# Busbar.net
KiCad netlist of a schematic drawn in Altium Designer
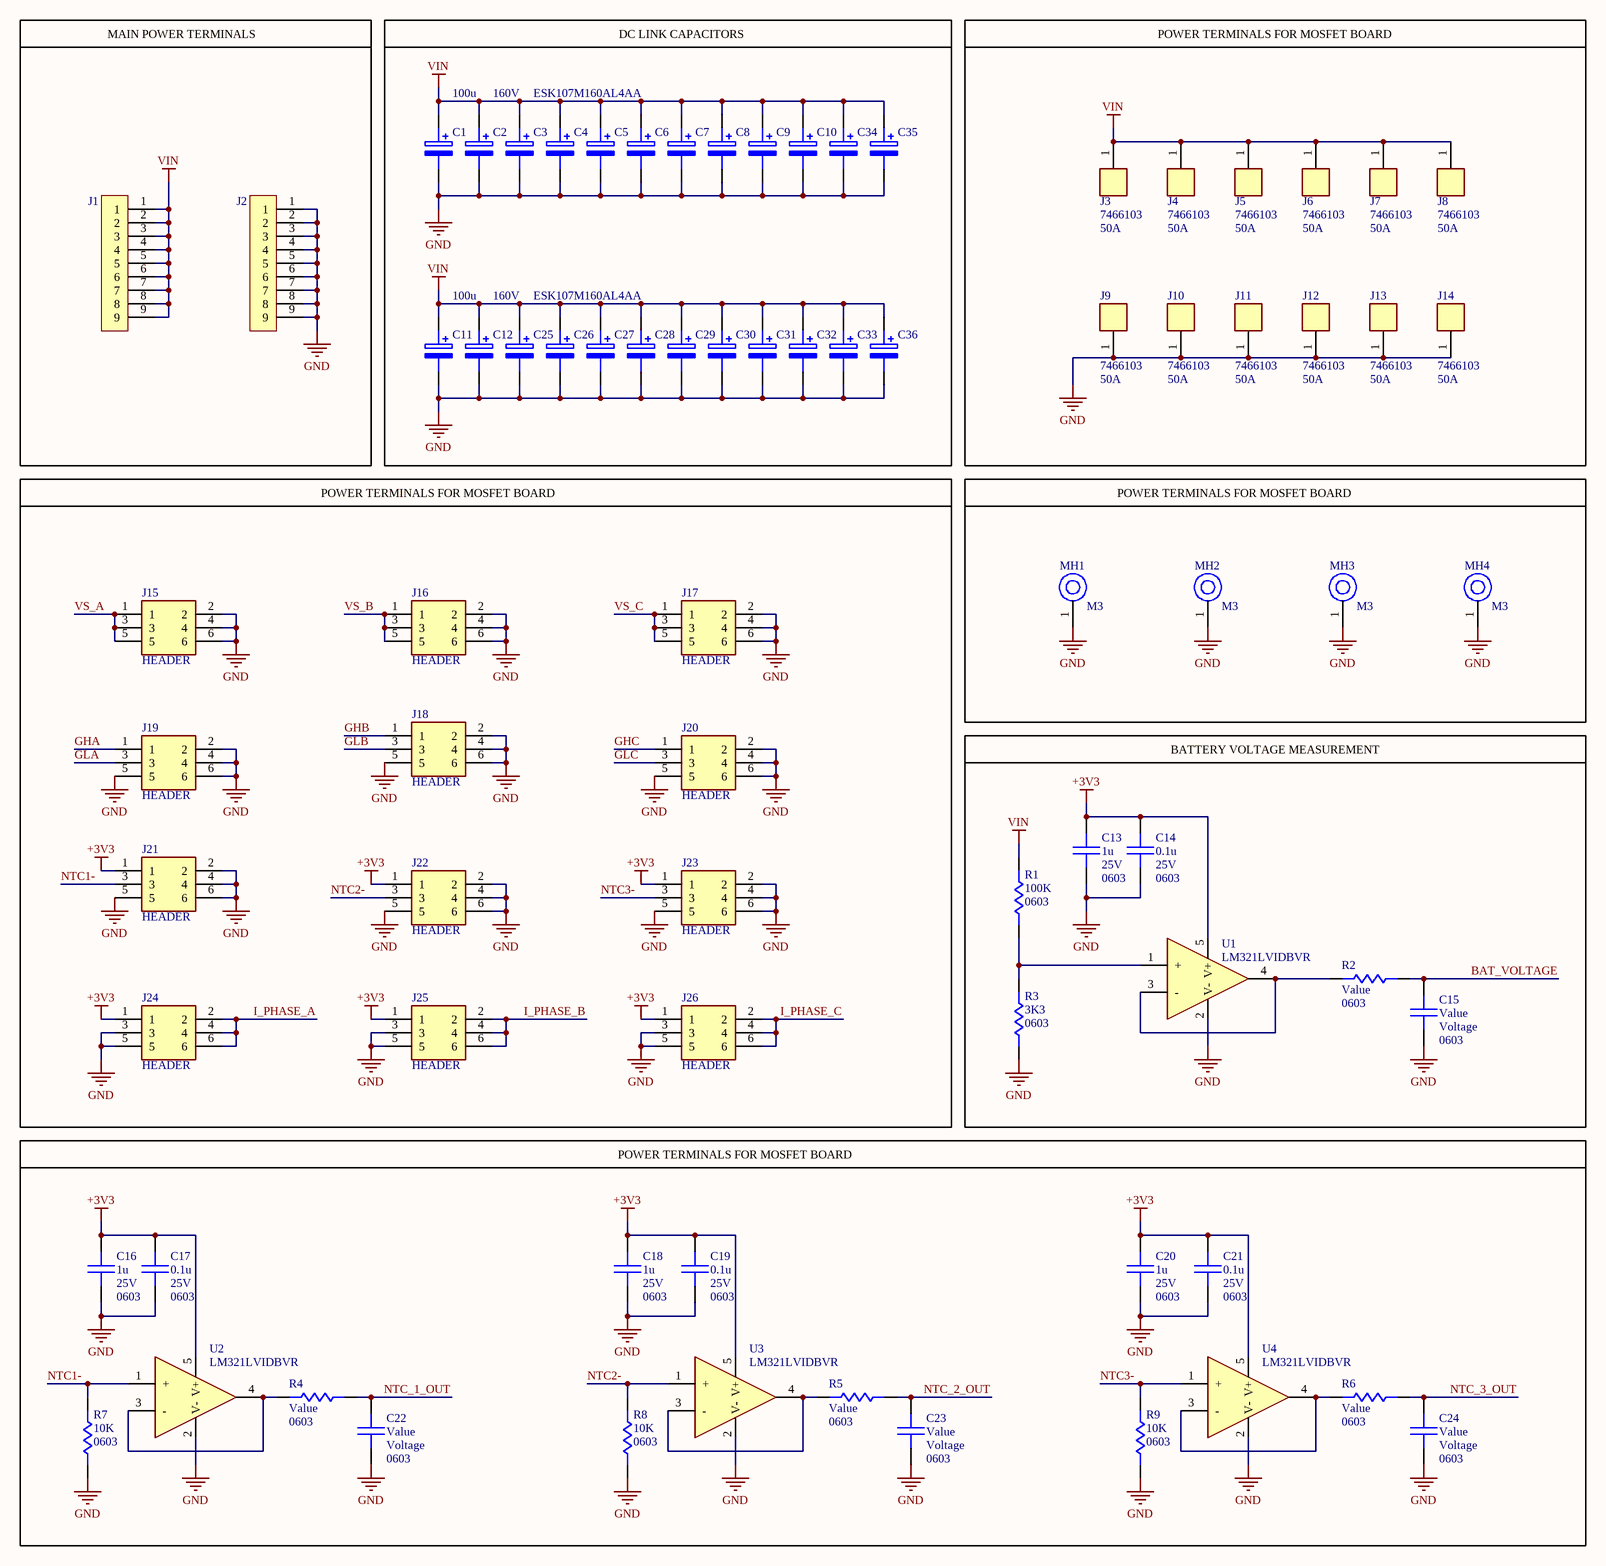
[diagram p0: Busbar.SchDoc]

(export (version "E")
  (design (tool "Eeschema 10.0.6"))
  (components
    (comp (ref "C1")
      (value "ESK107M160AL4AA")
      (footprint "C_THT_13X25X5")
      (description "Capacitor Polarised")
      (fields (field (name "ALTIUM_VALUE") "100u") (field (name "VOLTAGE") "160V"))
      (libsource (lib "My_Integrated_Lib") (part "CAP_POL_THT_100u_160V"))
    )
    (comp (ref "C2")
      (value "ESK107M160AL4AA")
      (footprint "C_THT_13X25X5")
      (description "Capacitor Polarised")
      (fields (field (name "VOLTAGE") "160V"))
      (libsource (lib "My_Integrated_Lib") (part "CAP_POL_THT_100u_160V"))
    )
    (comp (ref "C3")
      (value "ESK107M160AL4AA")
      (footprint "C_THT_13X25X5")
      (description "Capacitor Polarised")
      (fields (field (name "VOLTAGE") "160V"))
      (libsource (lib "My_Integrated_Lib") (part "CAP_POL_THT_100u_160V"))
    )
    (comp (ref "C4")
      (value "ESK107M160AL4AA")
      (footprint "C_THT_13X25X5")
      (description "Capacitor Polarised")
      (fields (field (name "VOLTAGE") "160V"))
      (libsource (lib "My_Integrated_Lib") (part "CAP_POL_THT_100u_160V"))
    )
    (comp (ref "C5")
      (value "ESK107M160AL4AA")
      (footprint "C_THT_13X25X5")
      (description "Capacitor Polarised")
      (fields (field (name "VOLTAGE") "160V"))
      (libsource (lib "My_Integrated_Lib") (part "CAP_POL_THT_100u_160V"))
    )
    (comp (ref "C6")
      (value "ESK107M160AL4AA")
      (footprint "C_THT_13X25X5")
      (description "Capacitor Polarised")
      (fields (field (name "VOLTAGE") "160V"))
      (libsource (lib "My_Integrated_Lib") (part "CAP_POL_THT_100u_160V"))
    )
    (comp (ref "C7")
      (value "ESK107M160AL4AA")
      (footprint "C_THT_13X25X5")
      (description "Capacitor Polarised")
      (fields (field (name "VOLTAGE") "160V"))
      (libsource (lib "My_Integrated_Lib") (part "CAP_POL_THT_100u_160V"))
    )
    (comp (ref "C8")
      (value "ESK107M160AL4AA")
      (footprint "C_THT_13X25X5")
      (description "Capacitor Polarised")
      (fields (field (name "VOLTAGE") "160V"))
      (libsource (lib "My_Integrated_Lib") (part "CAP_POL_THT_100u_160V"))
    )
    (comp (ref "C9")
      (value "ESK107M160AL4AA")
      (footprint "C_THT_13X25X5")
      (description "Capacitor Polarised")
      (fields (field (name "VOLTAGE") "160V"))
      (libsource (lib "My_Integrated_Lib") (part "CAP_POL_THT_100u_160V"))
    )
    (comp (ref "C10")
      (value "ESK107M160AL4AA")
      (footprint "C_THT_13X25X5")
      (description "Capacitor Polarised")
      (fields (field (name "VOLTAGE") "160V"))
      (libsource (lib "My_Integrated_Lib") (part "CAP_POL_THT_100u_160V"))
    )
    (comp (ref "C11")
      (value "ESK107M160AL4AA")
      (footprint "C_THT_13X25X5")
      (description "Capacitor Polarised")
      (fields (field (name "ALTIUM_VALUE") "100u") (field (name "VOLTAGE") "160V"))
      (libsource (lib "My_Integrated_Lib") (part "CAP_POL_THT_100u_160V"))
    )
    (comp (ref "C12")
      (value "ESK107M160AL4AA")
      (footprint "C_THT_13X25X5")
      (description "Capacitor Polarised")
      (fields (field (name "VOLTAGE") "160V"))
      (libsource (lib "My_Integrated_Lib") (part "CAP_POL_THT_100u_160V"))
    )
    (comp (ref "C13")
      (value "0603")
      (footprint "C_0603")
      (description "SMD Chip Capacitor - 0603")
      (fields (field (name "VOLTAGE") "25V") (field (name "ALTIUM_VALUE") "1u"))
      (libsource (lib "My_Integrated_Lib") (part "CAP_0603"))
    )
    (comp (ref "C14")
      (value "0603")
      (footprint "C_0603")
      (description "SMD Chip Capacitor - 0603")
      (fields (field (name "VOLTAGE") "25V") (field (name "ALTIUM_VALUE") "0.1u"))
      (libsource (lib "My_Integrated_Lib") (part "CAP_0603"))
    )
    (comp (ref "C15")
      (value "0603")
      (footprint "C_0603")
      (description "SMD Chip Capacitor - 0603")
      (fields (field (name "VOLTAGE") "Voltage") (field (name "ALTIUM_VALUE") "Value"))
      (libsource (lib "My_Integrated_Lib") (part "CAP_0603"))
    )
    (comp (ref "C16")
      (value "0603")
      (footprint "C_0603")
      (description "SMD Chip Capacitor - 0603")
      (fields (field (name "VOLTAGE") "25V") (field (name "ALTIUM_VALUE") "1u"))
      (libsource (lib "My_Integrated_Lib") (part "CAP_0603"))
    )
    (comp (ref "C17")
      (value "0603")
      (footprint "C_0603")
      (description "SMD Chip Capacitor - 0603")
      (fields (field (name "VOLTAGE") "25V") (field (name "ALTIUM_VALUE") "0.1u"))
      (libsource (lib "My_Integrated_Lib") (part "CAP_0603"))
    )
    (comp (ref "C18")
      (value "0603")
      (footprint "C_0603")
      (description "SMD Chip Capacitor - 0603")
      (fields (field (name "VOLTAGE") "25V") (field (name "ALTIUM_VALUE") "1u"))
      (libsource (lib "My_Integrated_Lib") (part "CAP_0603"))
    )
    (comp (ref "C19")
      (value "0603")
      (footprint "C_0603")
      (description "SMD Chip Capacitor - 0603")
      (fields (field (name "VOLTAGE") "25V") (field (name "ALTIUM_VALUE") "0.1u"))
      (libsource (lib "My_Integrated_Lib") (part "CAP_0603"))
    )
    (comp (ref "C20")
      (value "0603")
      (footprint "C_0603")
      (description "SMD Chip Capacitor - 0603")
      (fields (field (name "VOLTAGE") "25V") (field (name "ALTIUM_VALUE") "1u"))
      (libsource (lib "My_Integrated_Lib") (part "CAP_0603"))
    )
    (comp (ref "C21")
      (value "0603")
      (footprint "C_0603")
      (description "SMD Chip Capacitor - 0603")
      (fields (field (name "VOLTAGE") "25V") (field (name "ALTIUM_VALUE") "0.1u"))
      (libsource (lib "My_Integrated_Lib") (part "CAP_0603"))
    )
    (comp (ref "C22")
      (value "0603")
      (footprint "C_0603")
      (description "SMD Chip Capacitor - 0603")
      (fields (field (name "VOLTAGE") "Voltage") (field (name "ALTIUM_VALUE") "Value"))
      (libsource (lib "My_Integrated_Lib") (part "CAP_0603"))
    )
    (comp (ref "C23")
      (value "0603")
      (footprint "C_0603")
      (description "SMD Chip Capacitor - 0603")
      (fields (field (name "VOLTAGE") "Voltage") (field (name "ALTIUM_VALUE") "Value"))
      (libsource (lib "My_Integrated_Lib") (part "CAP_0603"))
    )
    (comp (ref "C24")
      (value "0603")
      (footprint "C_0603")
      (description "SMD Chip Capacitor - 0603")
      (fields (field (name "VOLTAGE") "Voltage") (field (name "ALTIUM_VALUE") "Value"))
      (libsource (lib "My_Integrated_Lib") (part "CAP_0603"))
    )
    (comp (ref "C25")
      (value "ESK107M160AL4AA")
      (footprint "C_THT_13X25X5")
      (description "Capacitor Polarised")
      (fields (field (name "VOLTAGE") "160V"))
      (libsource (lib "My_Integrated_Lib") (part "CAP_POL_THT_100u_160V"))
    )
    (comp (ref "C26")
      (value "ESK107M160AL4AA")
      (footprint "C_THT_13X25X5")
      (description "Capacitor Polarised")
      (fields (field (name "VOLTAGE") "160V"))
      (libsource (lib "My_Integrated_Lib") (part "CAP_POL_THT_100u_160V"))
    )
    (comp (ref "C27")
      (value "ESK107M160AL4AA")
      (footprint "C_THT_13X25X5")
      (description "Capacitor Polarised")
      (fields (field (name "VOLTAGE") "160V"))
      (libsource (lib "My_Integrated_Lib") (part "CAP_POL_THT_100u_160V"))
    )
    (comp (ref "C28")
      (value "ESK107M160AL4AA")
      (footprint "C_THT_13X25X5")
      (description "Capacitor Polarised")
      (fields (field (name "VOLTAGE") "160V"))
      (libsource (lib "My_Integrated_Lib") (part "CAP_POL_THT_100u_160V"))
    )
    (comp (ref "C29")
      (value "ESK107M160AL4AA")
      (footprint "C_THT_13X25X5")
      (description "Capacitor Polarised")
      (fields (field (name "VOLTAGE") "160V"))
      (libsource (lib "My_Integrated_Lib") (part "CAP_POL_THT_100u_160V"))
    )
    (comp (ref "C30")
      (value "ESK107M160AL4AA")
      (footprint "C_THT_13X25X5")
      (description "Capacitor Polarised")
      (fields (field (name "VOLTAGE") "160V"))
      (libsource (lib "My_Integrated_Lib") (part "CAP_POL_THT_100u_160V"))
    )
    (comp (ref "C31")
      (value "ESK107M160AL4AA")
      (footprint "C_THT_13X25X5")
      (description "Capacitor Polarised")
      (fields (field (name "VOLTAGE") "160V"))
      (libsource (lib "My_Integrated_Lib") (part "CAP_POL_THT_100u_160V"))
    )
    (comp (ref "C32")
      (value "ESK107M160AL4AA")
      (footprint "C_THT_13X25X5")
      (description "Capacitor Polarised")
      (fields (field (name "VOLTAGE") "160V"))
      (libsource (lib "My_Integrated_Lib") (part "CAP_POL_THT_100u_160V"))
    )
    (comp (ref "C33")
      (value "ESK107M160AL4AA")
      (footprint "C_THT_13X25X5")
      (description "Capacitor Polarised")
      (fields (field (name "VOLTAGE") "160V"))
      (libsource (lib "My_Integrated_Lib") (part "CAP_POL_THT_100u_160V"))
    )
    (comp (ref "C34")
      (value "ESK107M160AL4AA")
      (footprint "C_THT_13X25X5")
      (description "Capacitor Polarised")
      (fields (field (name "VOLTAGE") "160V"))
      (libsource (lib "My_Integrated_Lib") (part "CAP_POL_THT_100u_160V"))
    )
    (comp (ref "C35")
      (value "ESK107M160AL4AA")
      (footprint "C_THT_13X25X5")
      (description "Capacitor Polarised")
      (fields (field (name "VOLTAGE") "160V"))
      (libsource (lib "My_Integrated_Lib") (part "CAP_POL_THT_100u_160V"))
    )
    (comp (ref "C36")
      (value "ESK107M160AL4AA")
      (footprint "C_THT_13X25X5")
      (description "Capacitor Polarised")
      (fields (field (name "VOLTAGE") "160V"))
      (libsource (lib "My_Integrated_Lib") (part "CAP_POL_THT_100u_160V"))
    )
    (comp (ref "J1")
      (value "74651195R")
      (footprint "74651195R")
      (description "Terminals M5-13mm 85A")
      (libsource (lib "My_Integrated_Lib") (part "TERMINAL_74651195R"))
    )
    (comp (ref "J2")
      (value "74651195R")
      (footprint "74651195R")
      (description "Terminals M5-13mm 85A")
      (libsource (lib "My_Integrated_Lib") (part "TERMINAL_74651195R"))
    )
    (comp (ref "J3")
      (value "7466103")
      (footprint "PAD_D8.2_H3.4")
      (description "Terminals, SMT, M3 Thread, 50A")
      (fields (field (name "CURRENT") "50A"))
      (libsource (lib "") (part "TERMINAL_7466203_1"))
    )
    (comp (ref "J4")
      (value "7466103")
      (footprint "PAD_D8.2_H3.4")
      (description "Terminals, SMT, M3 Thread, 50A")
      (fields (field (name "CURRENT") "50A"))
      (libsource (lib "") (part "TERMINAL_7466203_1"))
    )
    (comp (ref "J5")
      (value "7466103")
      (footprint "PAD_D8.2_H3.4")
      (description "Terminals, SMT, M3 Thread, 50A")
      (fields (field (name "CURRENT") "50A"))
      (libsource (lib "") (part "TERMINAL_7466203_1"))
    )
    (comp (ref "J6")
      (value "7466103")
      (footprint "PAD_D8.2_H3.4")
      (description "Terminals, SMT, M3 Thread, 50A")
      (fields (field (name "CURRENT") "50A"))
      (libsource (lib "") (part "TERMINAL_7466203_1"))
    )
    (comp (ref "J7")
      (value "7466103")
      (footprint "PAD_D8.2_H3.4")
      (description "Terminals, SMT, M3 Thread, 50A")
      (fields (field (name "CURRENT") "50A"))
      (libsource (lib "") (part "TERMINAL_7466203_1"))
    )
    (comp (ref "J8")
      (value "7466103")
      (footprint "PAD_D8.2_H3.4")
      (description "Terminals, SMT, M3 Thread, 50A")
      (fields (field (name "CURRENT") "50A"))
      (libsource (lib "") (part "TERMINAL_7466203_1"))
    )
    (comp (ref "J9")
      (value "7466103")
      (footprint "PAD_D8.2_H3.4")
      (description "Terminals, SMT, M3 Thread, 50A")
      (fields (field (name "CURRENT") "50A"))
      (libsource (lib "My_Integrated_Lib") (part "TERMINAL_7466203"))
    )
    (comp (ref "J10")
      (value "7466103")
      (footprint "PAD_D8.2_H3.4")
      (description "Terminals, SMT, M3 Thread, 50A")
      (fields (field (name "CURRENT") "50A"))
      (libsource (lib "My_Integrated_Lib") (part "TERMINAL_7466203"))
    )
    (comp (ref "J11")
      (value "7466103")
      (footprint "PAD_D8.2_H3.4")
      (description "Terminals, SMT, M3 Thread, 50A")
      (fields (field (name "CURRENT") "50A"))
      (libsource (lib "My_Integrated_Lib") (part "TERMINAL_7466203"))
    )
    (comp (ref "J12")
      (value "7466103")
      (footprint "PAD_D8.2_H3.4")
      (description "Terminals, SMT, M3 Thread, 50A")
      (fields (field (name "CURRENT") "50A"))
      (libsource (lib "My_Integrated_Lib") (part "TERMINAL_7466203"))
    )
    (comp (ref "J13")
      (value "7466103")
      (footprint "PAD_D8.2_H3.4")
      (description "Terminals, SMT, M3 Thread, 50A")
      (fields (field (name "CURRENT") "50A"))
      (libsource (lib "My_Integrated_Lib") (part "TERMINAL_7466203"))
    )
    (comp (ref "J14")
      (value "7466103")
      (footprint "PAD_D8.2_H3.4")
      (description "Terminals, SMT, M3 Thread, 50A")
      (fields (field (name "CURRENT") "50A"))
      (libsource (lib "My_Integrated_Lib") (part "TERMINAL_7466203"))
    )
    (comp (ref "J15")
      (value "HEADER")
      (footprint "HEADER_FEMALE_SMD_2X3_1.27MM")
      (libsource (lib "My_Integrated_Lib") (part "HEADER_SMD_2X3_1.27MM"))
    )
    (comp (ref "J16")
      (value "HEADER")
      (footprint "HEADER_FEMALE_SMD_2X3_1.27MM")
      (libsource (lib "My_Integrated_Lib") (part "HEADER_SMD_2X3_1.27MM"))
    )
    (comp (ref "J17")
      (value "HEADER")
      (footprint "HEADER_FEMALE_SMD_2X3_1.27MM")
      (libsource (lib "My_Integrated_Lib") (part "HEADER_SMD_2X3_1.27MM"))
    )
    (comp (ref "J18")
      (value "HEADER")
      (footprint "HEADER_FEMALE_SMD_2X3_1.27MM")
      (libsource (lib "My_Integrated_Lib") (part "HEADER_SMD_2X3_1.27MM"))
    )
    (comp (ref "J19")
      (value "HEADER")
      (footprint "HEADER_FEMALE_SMD_2X3_1.27MM")
      (libsource (lib "My_Integrated_Lib") (part "HEADER_SMD_2X3_1.27MM"))
    )
    (comp (ref "J20")
      (value "HEADER")
      (footprint "HEADER_FEMALE_SMD_2X3_1.27MM")
      (libsource (lib "My_Integrated_Lib") (part "HEADER_SMD_2X3_1.27MM"))
    )
    (comp (ref "J21")
      (value "HEADER")
      (footprint "HEADER_FEMALE_SMD_2X3_1.27MM")
      (libsource (lib "My_Integrated_Lib") (part "HEADER_SMD_2X3_1.27MM"))
    )
    (comp (ref "J22")
      (value "HEADER")
      (footprint "HEADER_FEMALE_SMD_2X3_1.27MM")
      (libsource (lib "My_Integrated_Lib") (part "HEADER_SMD_2X3_1.27MM"))
    )
    (comp (ref "J23")
      (value "HEADER")
      (footprint "HEADER_FEMALE_SMD_2X3_1.27MM")
      (libsource (lib "My_Integrated_Lib") (part "HEADER_SMD_2X3_1.27MM"))
    )
    (comp (ref "J24")
      (value "HEADER")
      (footprint "HEADER_FEMALE_SMD_2X3_1.27MM")
      (libsource (lib "My_Integrated_Lib") (part "HEADER_SMD_2X3_1.27MM"))
    )
    (comp (ref "J25")
      (value "HEADER")
      (footprint "HEADER_FEMALE_SMD_2X3_1.27MM")
      (libsource (lib "My_Integrated_Lib") (part "HEADER_SMD_2X3_1.27MM"))
    )
    (comp (ref "J26")
      (value "HEADER")
      (footprint "HEADER_FEMALE_SMD_2X3_1.27MM")
      (libsource (lib "My_Integrated_Lib") (part "HEADER_SMD_2X3_1.27MM"))
    )
    (comp (ref "MH1")
      (value "M3")
      (footprint "MOUNTING_HOLE_M3")
      (description "M3 Mounting Hole")
      (libsource (lib "My_Integrated_Lib") (part "Mounting_Hole_M3"))
    )
    (comp (ref "MH2")
      (value "M3")
      (footprint "MOUNTING_HOLE_M3")
      (description "M3 Mounting Hole")
      (libsource (lib "My_Integrated_Lib") (part "Mounting_Hole_M3"))
    )
    (comp (ref "MH3")
      (value "M3")
      (footprint "MOUNTING_HOLE_M3")
      (description "M3 Mounting Hole")
      (libsource (lib "My_Integrated_Lib") (part "Mounting_Hole_M3"))
    )
    (comp (ref "MH4")
      (value "M3")
      (footprint "MOUNTING_HOLE_M3")
      (description "M3 Mounting Hole")
      (libsource (lib "My_Integrated_Lib") (part "Mounting_Hole_M3"))
    )
    (comp (ref "R1")
      (value "0603")
      (footprint "R_0603")
      (description "SMD Chip Resistor - 0603")
      (fields (field (name "TOLERANCE") "%1") (field (name "ALTIUM_VALUE") "100K"))
      (libsource (lib "My_Integrated_Lib") (part "RES_0603"))
    )
    (comp (ref "R2")
      (value "0603")
      (footprint "R_0603")
      (description "SMD Chip Resistor - 0603")
      (fields (field (name "TOLERANCE") "?") (field (name "ALTIUM_VALUE") "Value"))
      (libsource (lib "My_Integrated_Lib") (part "RES_0603"))
    )
    (comp (ref "R3")
      (value "0603")
      (footprint "R_0603")
      (description "SMD Chip Resistor - 0603")
      (fields (field (name "TOLERANCE") "%1") (field (name "ALTIUM_VALUE") "3K3"))
      (libsource (lib "My_Integrated_Lib") (part "RES_0603"))
    )
    (comp (ref "R4")
      (value "0603")
      (footprint "R_0603")
      (description "SMD Chip Resistor - 0603")
      (fields (field (name "TOLERANCE") "?") (field (name "ALTIUM_VALUE") "Value"))
      (libsource (lib "My_Integrated_Lib") (part "RES_0603"))
    )
    (comp (ref "R5")
      (value "0603")
      (footprint "R_0603")
      (description "SMD Chip Resistor - 0603")
      (fields (field (name "TOLERANCE") "?") (field (name "ALTIUM_VALUE") "Value"))
      (libsource (lib "My_Integrated_Lib") (part "RES_0603"))
    )
    (comp (ref "R6")
      (value "0603")
      (footprint "R_0603")
      (description "SMD Chip Resistor - 0603")
      (fields (field (name "TOLERANCE") "?") (field (name "ALTIUM_VALUE") "Value"))
      (libsource (lib "My_Integrated_Lib") (part "RES_0603"))
    )
    (comp (ref "R7")
      (value "0603")
      (footprint "R_0603")
      (description "SMD Chip Resistor - 0603")
      (fields (field (name "TOLERANCE") "%1") (field (name "ALTIUM_VALUE") "10K"))
      (libsource (lib "My_Integrated_Lib") (part "RES_0603"))
    )
    (comp (ref "R8")
      (value "0603")
      (footprint "R_0603")
      (description "SMD Chip Resistor - 0603")
      (fields (field (name "TOLERANCE") "%1") (field (name "ALTIUM_VALUE") "10K"))
      (libsource (lib "My_Integrated_Lib") (part "RES_0603"))
    )
    (comp (ref "R9")
      (value "0603")
      (footprint "R_0603")
      (description "SMD Chip Resistor - 0603")
      (fields (field (name "TOLERANCE") "%1") (field (name "ALTIUM_VALUE") "10K"))
      (libsource (lib "My_Integrated_Lib") (part "RES_0603"))
    )
    (comp (ref "U1")
      (value "LM321LVIDBVR")
      (footprint "SOT23-5")
      (description "Operational Amplifiers, Single 5.5-V, 1-MHz, 3-mV Offset Voltage")
      (libsource (lib "My_Integrated_Lib") (part "OPAMP_LM321LVIDBVR"))
    )
    (comp (ref "U2")
      (value "LM321LVIDBVR")
      (footprint "SOT23-5")
      (description "Operational Amplifiers, Single 5.5-V, 1-MHz, 3-mV Offset Voltage")
      (libsource (lib "My_Integrated_Lib") (part "OPAMP_LM321LVIDBVR"))
    )
    (comp (ref "U3")
      (value "LM321LVIDBVR")
      (footprint "SOT23-5")
      (description "Operational Amplifiers, Single 5.5-V, 1-MHz, 3-mV Offset Voltage")
      (libsource (lib "My_Integrated_Lib") (part "OPAMP_LM321LVIDBVR"))
    )
    (comp (ref "U4")
      (value "LM321LVIDBVR")
      (footprint "SOT23-5")
      (description "Operational Amplifiers, Single 5.5-V, 1-MHz, 3-mV Offset Voltage")
      (libsource (lib "My_Integrated_Lib") (part "OPAMP_LM321LVIDBVR"))
    )
  )
  (nets
    (net (code "1") (name "+3V3") (class "Default")
      (node (ref "C13") (pin "1") (pinfunction "1_1") (pintype "passive"))
      (node (ref "C14") (pin "1") (pinfunction "1_1") (pintype "passive"))
      (node (ref "C16") (pin "1") (pinfunction "1_1") (pintype "passive"))
      (node (ref "C17") (pin "1") (pinfunction "1_1") (pintype "passive"))
      (node (ref "C18") (pin "1") (pinfunction "1_1") (pintype "passive"))
      (node (ref "C19") (pin "1") (pinfunction "1_1") (pintype "passive"))
      (node (ref "C20") (pin "1") (pinfunction "1_1") (pintype "passive"))
      (node (ref "C21") (pin "1") (pinfunction "1_1") (pintype "passive"))
      (node (ref "J21") (pin "1") (pinfunction "1_1") (pintype "passive"))
      (node (ref "J22") (pin "1") (pinfunction "1_1") (pintype "passive"))
      (node (ref "J23") (pin "1") (pinfunction "1_1") (pintype "passive"))
      (node (ref "J24") (pin "1") (pinfunction "1_1") (pintype "passive"))
      (node (ref "J25") (pin "1") (pinfunction "1_1") (pintype "passive"))
      (node (ref "J26") (pin "1") (pinfunction "1_1") (pintype "passive"))
      (node (ref "U1") (pin "5") (pinfunction "V+_5") (pintype "passive"))
      (node (ref "U2") (pin "5") (pinfunction "V+_5") (pintype "passive"))
      (node (ref "U3") (pin "5") (pinfunction "V+_5") (pintype "passive"))
      (node (ref "U4") (pin "5") (pinfunction "V+_5") (pintype "passive"))
    )
    (net (code "2") (name "/BAT_VOLTAGE") (class "Default")
      (node (ref "C15") (pin "1") (pinfunction "1_1") (pintype "passive"))
      (node (ref "R2") (pin "2") (pinfunction "2_2") (pintype "passive"))
    )
    (net (code "3") (name "/GHA") (class "Default")
      (node (ref "J19") (pin "1") (pinfunction "1_1") (pintype "passive"))
    )
    (net (code "4") (name "/GHB") (class "Default")
      (node (ref "J18") (pin "1") (pinfunction "1_1") (pintype "passive"))
    )
    (net (code "5") (name "/GHC") (class "Default")
      (node (ref "J20") (pin "1") (pinfunction "1_1") (pintype "passive"))
    )
    (net (code "6") (name "/GLA") (class "Default")
      (node (ref "J19") (pin "3") (pinfunction "3_3") (pintype "passive"))
    )
    (net (code "7") (name "/GLB") (class "Default")
      (node (ref "J18") (pin "3") (pinfunction "3_3") (pintype "passive"))
    )
    (net (code "8") (name "/GLC") (class "Default")
      (node (ref "J20") (pin "3") (pinfunction "3_3") (pintype "passive"))
    )
    (net (code "9") (name "/I_PHASE_A") (class "Default")
      (node (ref "J24") (pin "2") (pinfunction "2_2") (pintype "passive"))
      (node (ref "J24") (pin "4") (pinfunction "4_4") (pintype "passive"))
      (node (ref "J24") (pin "6") (pinfunction "6_6") (pintype "passive"))
    )
    (net (code "10") (name "/I_PHASE_B") (class "Default")
      (node (ref "J25") (pin "2") (pinfunction "2_2") (pintype "passive"))
      (node (ref "J25") (pin "4") (pinfunction "4_4") (pintype "passive"))
      (node (ref "J25") (pin "6") (pinfunction "6_6") (pintype "passive"))
    )
    (net (code "11") (name "/I_PHASE_C") (class "Default")
      (node (ref "J26") (pin "2") (pinfunction "2_2") (pintype "passive"))
      (node (ref "J26") (pin "4") (pinfunction "4_4") (pintype "passive"))
      (node (ref "J26") (pin "6") (pinfunction "6_6") (pintype "passive"))
    )
    (net (code "12") (name "/NTC1-") (class "Default")
      (node (ref "J21") (pin "3") (pinfunction "3_3") (pintype "passive"))
      (node (ref "R7") (pin "2") (pinfunction "2_2") (pintype "passive"))
      (node (ref "U2") (pin "1") (pinfunction "+_1") (pintype "passive"))
    )
    (net (code "13") (name "/NTC2-") (class "Default")
      (node (ref "J22") (pin "3") (pinfunction "3_3") (pintype "passive"))
      (node (ref "R8") (pin "2") (pinfunction "2_2") (pintype "passive"))
      (node (ref "U3") (pin "1") (pinfunction "+_1") (pintype "passive"))
    )
    (net (code "14") (name "/NTC3-") (class "Default")
      (node (ref "J23") (pin "3") (pinfunction "3_3") (pintype "passive"))
      (node (ref "R9") (pin "2") (pinfunction "2_2") (pintype "passive"))
      (node (ref "U4") (pin "1") (pinfunction "+_1") (pintype "passive"))
    )
    (net (code "15") (name "/NTC_1_OUT") (class "Default")
      (node (ref "C22") (pin "1") (pinfunction "1_1") (pintype "passive"))
      (node (ref "R4") (pin "2") (pinfunction "2_2") (pintype "passive"))
    )
    (net (code "16") (name "/NTC_2_OUT") (class "Default")
      (node (ref "C23") (pin "1") (pinfunction "1_1") (pintype "passive"))
      (node (ref "R5") (pin "2") (pinfunction "2_2") (pintype "passive"))
    )
    (net (code "17") (name "/NTC_3_OUT") (class "Default")
      (node (ref "C24") (pin "1") (pinfunction "1_1") (pintype "passive"))
      (node (ref "R6") (pin "2") (pinfunction "2_2") (pintype "passive"))
    )
    (net (code "18") (name "/VS_A") (class "Default")
      (node (ref "J15") (pin "1") (pinfunction "1_1") (pintype "passive"))
      (node (ref "J15") (pin "3") (pinfunction "3_3") (pintype "passive"))
      (node (ref "J15") (pin "5") (pinfunction "5_5") (pintype "passive"))
    )
    (net (code "19") (name "/VS_B") (class "Default")
      (node (ref "J16") (pin "1") (pinfunction "1_1") (pintype "passive"))
      (node (ref "J16") (pin "3") (pinfunction "3_3") (pintype "passive"))
      (node (ref "J16") (pin "5") (pinfunction "5_5") (pintype "passive"))
    )
    (net (code "20") (name "/VS_C") (class "Default")
      (node (ref "J17") (pin "1") (pinfunction "1_1") (pintype "passive"))
      (node (ref "J17") (pin "3") (pinfunction "3_3") (pintype "passive"))
      (node (ref "J17") (pin "5") (pinfunction "5_5") (pintype "passive"))
    )
    (net (code "21") (name "GND") (class "Default")
      (node (ref "C1") (pin "2") (pinfunction "-_2") (pintype "passive"))
      (node (ref "C10") (pin "2") (pinfunction "-_2") (pintype "passive"))
      (node (ref "C11") (pin "2") (pinfunction "-_2") (pintype "passive"))
      (node (ref "C12") (pin "2") (pinfunction "-_2") (pintype "passive"))
      (node (ref "C13") (pin "2") (pinfunction "2_2") (pintype "passive"))
      (node (ref "C14") (pin "2") (pinfunction "2_2") (pintype "passive"))
      (node (ref "C15") (pin "2") (pinfunction "2_2") (pintype "passive"))
      (node (ref "C16") (pin "2") (pinfunction "2_2") (pintype "passive"))
      (node (ref "C17") (pin "2") (pinfunction "2_2") (pintype "passive"))
      (node (ref "C18") (pin "2") (pinfunction "2_2") (pintype "passive"))
      (node (ref "C19") (pin "2") (pinfunction "2_2") (pintype "passive"))
      (node (ref "C2") (pin "2") (pinfunction "-_2") (pintype "passive"))
      (node (ref "C20") (pin "2") (pinfunction "2_2") (pintype "passive"))
      (node (ref "C21") (pin "2") (pinfunction "2_2") (pintype "passive"))
      (node (ref "C22") (pin "2") (pinfunction "2_2") (pintype "passive"))
      (node (ref "C23") (pin "2") (pinfunction "2_2") (pintype "passive"))
      (node (ref "C24") (pin "2") (pinfunction "2_2") (pintype "passive"))
      (node (ref "C25") (pin "2") (pinfunction "-_2") (pintype "passive"))
      (node (ref "C26") (pin "2") (pinfunction "-_2") (pintype "passive"))
      (node (ref "C27") (pin "2") (pinfunction "-_2") (pintype "passive"))
      (node (ref "C28") (pin "2") (pinfunction "-_2") (pintype "passive"))
      (node (ref "C29") (pin "2") (pinfunction "-_2") (pintype "passive"))
      (node (ref "C3") (pin "2") (pinfunction "-_2") (pintype "passive"))
      (node (ref "C30") (pin "2") (pinfunction "-_2") (pintype "passive"))
      (node (ref "C31") (pin "2") (pinfunction "-_2") (pintype "passive"))
      (node (ref "C32") (pin "2") (pinfunction "-_2") (pintype "passive"))
      (node (ref "C33") (pin "2") (pinfunction "-_2") (pintype "passive"))
      (node (ref "C34") (pin "2") (pinfunction "-_2") (pintype "passive"))
      (node (ref "C35") (pin "2") (pinfunction "-_2") (pintype "passive"))
      (node (ref "C36") (pin "2") (pinfunction "-_2") (pintype "passive"))
      (node (ref "C4") (pin "2") (pinfunction "-_2") (pintype "passive"))
      (node (ref "C5") (pin "2") (pinfunction "-_2") (pintype "passive"))
      (node (ref "C6") (pin "2") (pinfunction "-_2") (pintype "passive"))
      (node (ref "C7") (pin "2") (pinfunction "-_2") (pintype "passive"))
      (node (ref "C8") (pin "2") (pinfunction "-_2") (pintype "passive"))
      (node (ref "C9") (pin "2") (pinfunction "-_2") (pintype "passive"))
      (node (ref "J10") (pin "1") (pinfunction "1_1") (pintype "passive"))
      (node (ref "J11") (pin "1") (pinfunction "1_1") (pintype "passive"))
      (node (ref "J12") (pin "1") (pinfunction "1_1") (pintype "passive"))
      (node (ref "J13") (pin "1") (pinfunction "1_1") (pintype "passive"))
      (node (ref "J14") (pin "1") (pinfunction "1_1") (pintype "passive"))
      (node (ref "J15") (pin "2") (pinfunction "2_2") (pintype "passive"))
      (node (ref "J15") (pin "4") (pinfunction "4_4") (pintype "passive"))
      (node (ref "J15") (pin "6") (pinfunction "6_6") (pintype "passive"))
      (node (ref "J16") (pin "2") (pinfunction "2_2") (pintype "passive"))
      (node (ref "J16") (pin "4") (pinfunction "4_4") (pintype "passive"))
      (node (ref "J16") (pin "6") (pinfunction "6_6") (pintype "passive"))
      (node (ref "J17") (pin "2") (pinfunction "2_2") (pintype "passive"))
      (node (ref "J17") (pin "4") (pinfunction "4_4") (pintype "passive"))
      (node (ref "J17") (pin "6") (pinfunction "6_6") (pintype "passive"))
      (node (ref "J18") (pin "2") (pinfunction "2_2") (pintype "passive"))
      (node (ref "J18") (pin "4") (pinfunction "4_4") (pintype "passive"))
      (node (ref "J18") (pin "5") (pinfunction "5_5") (pintype "passive"))
      (node (ref "J18") (pin "6") (pinfunction "6_6") (pintype "passive"))
      (node (ref "J19") (pin "2") (pinfunction "2_2") (pintype "passive"))
      (node (ref "J19") (pin "4") (pinfunction "4_4") (pintype "passive"))
      (node (ref "J19") (pin "5") (pinfunction "5_5") (pintype "passive"))
      (node (ref "J19") (pin "6") (pinfunction "6_6") (pintype "passive"))
      (node (ref "J2") (pin "1") (pinfunction "1_1") (pintype "passive"))
      (node (ref "J2") (pin "2") (pinfunction "2_2") (pintype "passive"))
      (node (ref "J2") (pin "3") (pinfunction "3_3") (pintype "passive"))
      (node (ref "J2") (pin "4") (pinfunction "4_4") (pintype "passive"))
      (node (ref "J2") (pin "5") (pinfunction "5_5") (pintype "passive"))
      (node (ref "J2") (pin "6") (pinfunction "6_6") (pintype "passive"))
      (node (ref "J2") (pin "7") (pinfunction "7_7") (pintype "passive"))
      (node (ref "J2") (pin "8") (pinfunction "8_8") (pintype "passive"))
      (node (ref "J2") (pin "9") (pinfunction "9_9") (pintype "passive"))
      (node (ref "J20") (pin "2") (pinfunction "2_2") (pintype "passive"))
      (node (ref "J20") (pin "4") (pinfunction "4_4") (pintype "passive"))
      (node (ref "J20") (pin "5") (pinfunction "5_5") (pintype "passive"))
      (node (ref "J20") (pin "6") (pinfunction "6_6") (pintype "passive"))
      (node (ref "J21") (pin "2") (pinfunction "2_2") (pintype "passive"))
      (node (ref "J21") (pin "4") (pinfunction "4_4") (pintype "passive"))
      (node (ref "J21") (pin "5") (pinfunction "5_5") (pintype "passive"))
      (node (ref "J21") (pin "6") (pinfunction "6_6") (pintype "passive"))
      (node (ref "J22") (pin "2") (pinfunction "2_2") (pintype "passive"))
      (node (ref "J22") (pin "4") (pinfunction "4_4") (pintype "passive"))
      (node (ref "J22") (pin "5") (pinfunction "5_5") (pintype "passive"))
      (node (ref "J22") (pin "6") (pinfunction "6_6") (pintype "passive"))
      (node (ref "J23") (pin "2") (pinfunction "2_2") (pintype "passive"))
      (node (ref "J23") (pin "4") (pinfunction "4_4") (pintype "passive"))
      (node (ref "J23") (pin "5") (pinfunction "5_5") (pintype "passive"))
      (node (ref "J23") (pin "6") (pinfunction "6_6") (pintype "passive"))
      (node (ref "J24") (pin "3") (pinfunction "3_3") (pintype "passive"))
      (node (ref "J24") (pin "5") (pinfunction "5_5") (pintype "passive"))
      (node (ref "J25") (pin "3") (pinfunction "3_3") (pintype "passive"))
      (node (ref "J25") (pin "5") (pinfunction "5_5") (pintype "passive"))
      (node (ref "J26") (pin "3") (pinfunction "3_3") (pintype "passive"))
      (node (ref "J26") (pin "5") (pinfunction "5_5") (pintype "passive"))
      (node (ref "J9") (pin "1") (pinfunction "1_1") (pintype "passive"))
      (node (ref "MH1") (pin "1") (pintype "passive"))
      (node (ref "MH2") (pin "1") (pintype "passive"))
      (node (ref "MH3") (pin "1") (pintype "passive"))
      (node (ref "MH4") (pin "1") (pintype "passive"))
      (node (ref "R3") (pin "1") (pinfunction "1_1") (pintype "passive"))
      (node (ref "R7") (pin "1") (pinfunction "1_1") (pintype "passive"))
      (node (ref "R8") (pin "1") (pinfunction "1_1") (pintype "passive"))
      (node (ref "R9") (pin "1") (pinfunction "1_1") (pintype "passive"))
      (node (ref "U1") (pin "2") (pinfunction "V-_2") (pintype "passive"))
      (node (ref "U2") (pin "2") (pinfunction "V-_2") (pintype "passive"))
      (node (ref "U3") (pin "2") (pinfunction "V-_2") (pintype "passive"))
      (node (ref "U4") (pin "2") (pinfunction "V-_2") (pintype "passive"))
    )
    (net (code "22") (name "Net-(U1-+)") (class "Default")
      (node (ref "R1") (pin "1") (pinfunction "1_1") (pintype "passive"))
      (node (ref "R3") (pin "2") (pinfunction "2_2") (pintype "passive"))
      (node (ref "U1") (pin "1") (pinfunction "+_1") (pintype "passive"))
    )
    (net (code "23") (name "Net-(U1--)") (class "Default")
      (node (ref "R2") (pin "1") (pinfunction "1_1") (pintype "passive"))
      (node (ref "U1") (pin "3") (pinfunction "-_3") (pintype "passive"))
      (node (ref "U1") (pin "4") (pinfunction "OUT_4") (pintype "passive"))
    )
    (net (code "24") (name "Net-(U2--)") (class "Default")
      (node (ref "R4") (pin "1") (pinfunction "1_1") (pintype "passive"))
      (node (ref "U2") (pin "3") (pinfunction "-_3") (pintype "passive"))
      (node (ref "U2") (pin "4") (pinfunction "OUT_4") (pintype "passive"))
    )
    (net (code "25") (name "Net-(U3--)") (class "Default")
      (node (ref "R5") (pin "1") (pinfunction "1_1") (pintype "passive"))
      (node (ref "U3") (pin "3") (pinfunction "-_3") (pintype "passive"))
      (node (ref "U3") (pin "4") (pinfunction "OUT_4") (pintype "passive"))
    )
    (net (code "26") (name "Net-(U4--)") (class "Default")
      (node (ref "R6") (pin "1") (pinfunction "1_1") (pintype "passive"))
      (node (ref "U4") (pin "3") (pinfunction "-_3") (pintype "passive"))
      (node (ref "U4") (pin "4") (pinfunction "OUT_4") (pintype "passive"))
    )
    (net (code "27") (name "VIN") (class "Default")
      (node (ref "C1") (pin "1") (pinfunction "+_1") (pintype "passive"))
      (node (ref "C10") (pin "1") (pinfunction "+_1") (pintype "passive"))
      (node (ref "C11") (pin "1") (pinfunction "+_1") (pintype "passive"))
      (node (ref "C12") (pin "1") (pinfunction "+_1") (pintype "passive"))
      (node (ref "C2") (pin "1") (pinfunction "+_1") (pintype "passive"))
      (node (ref "C25") (pin "1") (pinfunction "+_1") (pintype "passive"))
      (node (ref "C26") (pin "1") (pinfunction "+_1") (pintype "passive"))
      (node (ref "C27") (pin "1") (pinfunction "+_1") (pintype "passive"))
      (node (ref "C28") (pin "1") (pinfunction "+_1") (pintype "passive"))
      (node (ref "C29") (pin "1") (pinfunction "+_1") (pintype "passive"))
      (node (ref "C3") (pin "1") (pinfunction "+_1") (pintype "passive"))
      (node (ref "C30") (pin "1") (pinfunction "+_1") (pintype "passive"))
      (node (ref "C31") (pin "1") (pinfunction "+_1") (pintype "passive"))
      (node (ref "C32") (pin "1") (pinfunction "+_1") (pintype "passive"))
      (node (ref "C33") (pin "1") (pinfunction "+_1") (pintype "passive"))
      (node (ref "C34") (pin "1") (pinfunction "+_1") (pintype "passive"))
      (node (ref "C35") (pin "1") (pinfunction "+_1") (pintype "passive"))
      (node (ref "C36") (pin "1") (pinfunction "+_1") (pintype "passive"))
      (node (ref "C4") (pin "1") (pinfunction "+_1") (pintype "passive"))
      (node (ref "C5") (pin "1") (pinfunction "+_1") (pintype "passive"))
      (node (ref "C6") (pin "1") (pinfunction "+_1") (pintype "passive"))
      (node (ref "C7") (pin "1") (pinfunction "+_1") (pintype "passive"))
      (node (ref "C8") (pin "1") (pinfunction "+_1") (pintype "passive"))
      (node (ref "C9") (pin "1") (pinfunction "+_1") (pintype "passive"))
      (node (ref "J1") (pin "1") (pinfunction "1_1") (pintype "passive"))
      (node (ref "J1") (pin "2") (pinfunction "2_2") (pintype "passive"))
      (node (ref "J1") (pin "3") (pinfunction "3_3") (pintype "passive"))
      (node (ref "J1") (pin "4") (pinfunction "4_4") (pintype "passive"))
      (node (ref "J1") (pin "5") (pinfunction "5_5") (pintype "passive"))
      (node (ref "J1") (pin "6") (pinfunction "6_6") (pintype "passive"))
      (node (ref "J1") (pin "7") (pinfunction "7_7") (pintype "passive"))
      (node (ref "J1") (pin "8") (pinfunction "8_8") (pintype "passive"))
      (node (ref "J1") (pin "9") (pinfunction "9_9") (pintype "passive"))
      (node (ref "J3") (pin "1") (pinfunction "1_1") (pintype "passive"))
      (node (ref "J4") (pin "1") (pinfunction "1_1") (pintype "passive"))
      (node (ref "J5") (pin "1") (pinfunction "1_1") (pintype "passive"))
      (node (ref "J6") (pin "1") (pinfunction "1_1") (pintype "passive"))
      (node (ref "J7") (pin "1") (pinfunction "1_1") (pintype "passive"))
      (node (ref "J8") (pin "1") (pinfunction "1_1") (pintype "passive"))
      (node (ref "R1") (pin "2") (pinfunction "2_2") (pintype "passive"))
    )
  )
)
